# tms-rgb-jig.net
KiCad netlist of a schematic drawn in EAGLE
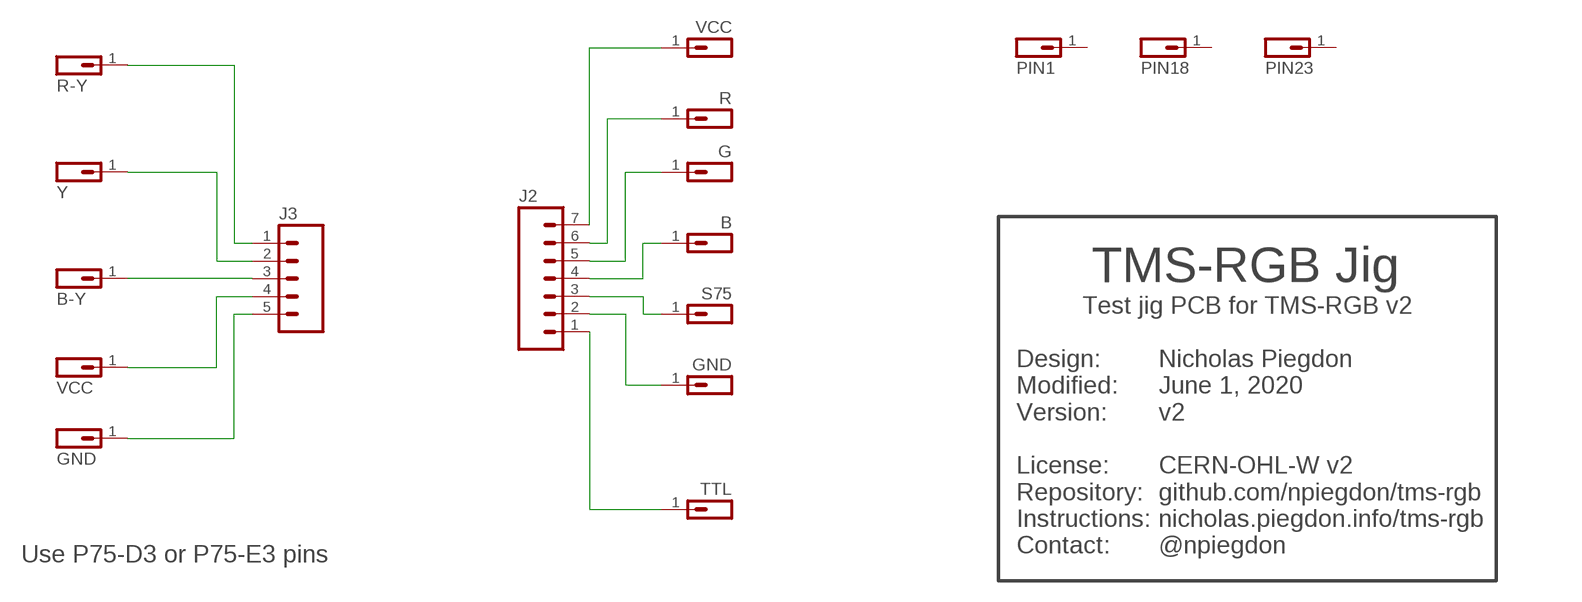
[diagram p0: schematic, sheet 1]

(export (version "E")
  (design (tool "Eeschema 10.0.6"))
  (components
    (comp (ref "J2")
      (value "CONN_07")
      (footprint "eagle-import:1X07")
      (libsource (lib "eagle-import") (part "CONN_07"))
    )
    (comp (ref "J3")
      (value "CONN_05")
      (footprint "eagle-import:1X05")
      (libsource (lib "eagle-import") (part "CONN_05"))
    )
    (comp (ref "J4")
      (value "R-Y")
      (footprint "eagle-import:POGO")
      (libsource (lib "eagle-import") (part "CONN_POGO"))
    )
    (comp (ref "J5")
      (value "B-Y")
      (footprint "eagle-import:POGO")
      (libsource (lib "eagle-import") (part "CONN_POGO"))
    )
    (comp (ref "J6")
      (value "Y")
      (footprint "eagle-import:POGO")
      (libsource (lib "eagle-import") (part "CONN_POGO"))
    )
    (comp (ref "J7")
      (value "VCC")
      (footprint "eagle-import:POGO")
      (libsource (lib "eagle-import") (part "CONN_POGO"))
    )
    (comp (ref "J8")
      (value "GND")
      (footprint "eagle-import:POGO")
      (libsource (lib "eagle-import") (part "CONN_POGO"))
    )
    (comp (ref "J9")
      (value "VCC")
      (footprint "eagle-import:POGO")
      (libsource (lib "eagle-import") (part "CONN_POGO"))
    )
    (comp (ref "J10")
      (value "R")
      (footprint "eagle-import:POGO")
      (libsource (lib "eagle-import") (part "CONN_POGO"))
    )
    (comp (ref "J11")
      (value "G")
      (footprint "eagle-import:POGO")
      (libsource (lib "eagle-import") (part "CONN_POGO"))
    )
    (comp (ref "J12")
      (value "B")
      (footprint "eagle-import:POGO")
      (libsource (lib "eagle-import") (part "CONN_POGO"))
    )
    (comp (ref "J13")
      (value "S75")
      (footprint "eagle-import:POGO")
      (libsource (lib "eagle-import") (part "CONN_POGO"))
    )
    (comp (ref "J14")
      (value "GND")
      (footprint "eagle-import:POGO")
      (libsource (lib "eagle-import") (part "CONN_POGO"))
    )
    (comp (ref "J15")
      (value "TTL")
      (footprint "eagle-import:POGO")
      (libsource (lib "eagle-import") (part "CONN_POGO"))
    )
    (comp (ref "J16")
      (value "PIN1")
      (footprint "eagle-import:POGO")
      (libsource (lib "eagle-import") (part "CONN_POGO"))
    )
    (comp (ref "J17")
      (value "PIN18")
      (footprint "eagle-import:POGO")
      (libsource (lib "eagle-import") (part "CONN_POGO"))
    )
    (comp (ref "J18")
      (value "PIN23")
      (footprint "eagle-import:POGO")
      (libsource (lib "eagle-import") (part "CONN_POGO"))
    )
  )
  (nets
    (net (code "1") (name "Net-(J4-5)") (class "Default")
      (node (ref "J3") (pin "1") (pinfunction "1_1") (pintype "passive"))
      (node (ref "J4") (pin "1") (pinfunction "5_1") (pintype "passive"))
    )
    (net (code "2") (name "Net-(J5-5)") (class "Default")
      (node (ref "J3") (pin "3") (pinfunction "3_3") (pintype "passive"))
      (node (ref "J5") (pin "1") (pinfunction "5_1") (pintype "passive"))
    )
    (net (code "3") (name "Net-(J6-5)") (class "Default")
      (node (ref "J3") (pin "2") (pinfunction "2_2") (pintype "passive"))
      (node (ref "J6") (pin "1") (pinfunction "5_1") (pintype "passive"))
    )
    (net (code "4") (name "Net-(J7-5)") (class "Default")
      (node (ref "J3") (pin "4") (pinfunction "4_4") (pintype "passive"))
      (node (ref "J7") (pin "1") (pinfunction "5_1") (pintype "passive"))
    )
    (net (code "5") (name "Net-(J8-5)") (class "Default")
      (node (ref "J3") (pin "5") (pinfunction "5_5") (pintype "passive"))
      (node (ref "J8") (pin "1") (pinfunction "5_1") (pintype "passive"))
    )
    (net (code "6") (name "Net-(J9-5)") (class "Default")
      (node (ref "J2") (pin "7") (pinfunction "7_7") (pintype "passive"))
      (node (ref "J9") (pin "1") (pinfunction "5_1") (pintype "passive"))
    )
    (net (code "7") (name "Net-(J10-5)") (class "Default")
      (node (ref "J10") (pin "1") (pinfunction "5_1") (pintype "passive"))
      (node (ref "J2") (pin "6") (pinfunction "6_6") (pintype "passive"))
    )
    (net (code "8") (name "Net-(J11-5)") (class "Default")
      (node (ref "J11") (pin "1") (pinfunction "5_1") (pintype "passive"))
      (node (ref "J2") (pin "5") (pinfunction "5_5") (pintype "passive"))
    )
    (net (code "9") (name "Net-(J12-5)") (class "Default")
      (node (ref "J12") (pin "1") (pinfunction "5_1") (pintype "passive"))
      (node (ref "J2") (pin "4") (pinfunction "4_4") (pintype "passive"))
    )
    (net (code "10") (name "Net-(J13-5)") (class "Default")
      (node (ref "J13") (pin "1") (pinfunction "5_1") (pintype "passive"))
      (node (ref "J2") (pin "3") (pinfunction "3_3") (pintype "passive"))
    )
    (net (code "11") (name "Net-(J14-5)") (class "Default")
      (node (ref "J14") (pin "1") (pinfunction "5_1") (pintype "passive"))
      (node (ref "J2") (pin "2") (pinfunction "2_2") (pintype "passive"))
    )
    (net (code "12") (name "Net-(J15-5)") (class "Default")
      (node (ref "J15") (pin "1") (pinfunction "5_1") (pintype "passive"))
      (node (ref "J2") (pin "1") (pinfunction "1_1") (pintype "passive"))
    )
    (net (code "13") (name "unconnected-(J16-5-Pad1)") (class "Default")
      (node (ref "J16") (pin "1") (pinfunction "5_1") (pintype "passive"))
    )
    (net (code "14") (name "unconnected-(J17-5-Pad1)") (class "Default")
      (node (ref "J17") (pin "1") (pinfunction "5_1") (pintype "passive"))
    )
    (net (code "15") (name "unconnected-(J18-5-Pad1)") (class "Default")
      (node (ref "J18") (pin "1") (pinfunction "5_1") (pintype "passive"))
    )
  )
)
